# devre.net
KiCad netlist of a schematic drawn in EAGLE
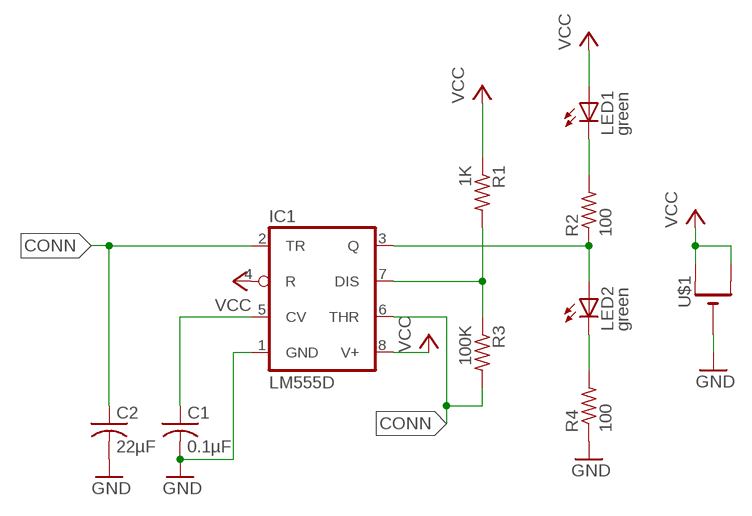
[diagram p0: schematic, sheet 1]

(export (version "E")
  (design (tool "Eeschema 10.0.6"))
  (components
    (comp (ref "C1")
      (value "0.1µF")
      (footprint "eagle-import:C0805")
      (libsource (lib "eagle-import") (part "C-USC0805"))
    )
    (comp (ref "C2")
      (value "22µF")
      (footprint "eagle-import:C0805")
      (libsource (lib "eagle-import") (part "C-USC0805"))
    )
    (comp (ref "IC1")
      (value "LM555D")
      (footprint "eagle-import:SO08")
      (libsource (lib "eagle-import") (part "555DLM"))
    )
    (comp (ref "LED1")
      (value "green")
      (footprint "eagle-import:CHIP-LED0805")
      (libsource (lib "eagle-import") (part "LEDCHIP-LED0805"))
    )
    (comp (ref "LED2")
      (value "green")
      (footprint "eagle-import:CHIP-LED0805")
      (libsource (lib "eagle-import") (part "LEDCHIP-LED0805"))
    )
    (comp (ref "R1")
      (value "1K")
      (footprint "eagle-import:R0805")
      (libsource (lib "eagle-import") (part "R-US_R0805"))
    )
    (comp (ref "R2")
      (value "100")
      (footprint "eagle-import:R0805")
      (libsource (lib "eagle-import") (part "R-US_R0805"))
    )
    (comp (ref "R3")
      (value "100K")
      (footprint "eagle-import:R0805")
      (libsource (lib "eagle-import") (part "R-US_R0805"))
    )
    (comp (ref "R4")
      (value "100")
      (footprint "eagle-import:R0805")
      (libsource (lib "eagle-import") (part "R-US_R0805"))
    )
    (comp (ref "U$1")
      (value "CR1220SMT")
      (footprint "eagle-import:CR1220-SMD")
      (libsource (lib "eagle-import") (part "CR1220SMT"))
    )
  )
  (nets
    (net (code "1") (name "CONN") (class "Default")
      (node (ref "C2") (pin "1") (pinfunction "1_1") (pintype "passive"))
      (node (ref "IC1") (pin "2") (pinfunction "TR_2") (pintype "input"))
      (node (ref "IC1") (pin "6") (pinfunction "THR_6") (pintype "input"))
      (node (ref "R3") (pin "2") (pinfunction "2_2") (pintype "passive"))
    )
    (net (code "2") (name "GND") (class "Default")
      (node (ref "C1") (pin "2") (pinfunction "2_2") (pintype "passive"))
      (node (ref "C2") (pin "2") (pinfunction "2_2") (pintype "passive"))
      (node (ref "IC1") (pin "1") (pinfunction "GND_1") (pintype "power_in"))
      (node (ref "R4") (pin "1") (pinfunction "1_1") (pintype "passive"))
      (node (ref "U$1") (pin "-") (pinfunction "-_-") (pintype "passive"))
    )
    (net (code "3") (name "Net-(IC1-CV)") (class "Default")
      (node (ref "C1") (pin "1") (pinfunction "1_1") (pintype "passive"))
      (node (ref "IC1") (pin "5") (pinfunction "CV_5") (pintype "input"))
    )
    (net (code "4") (name "Net-(IC1-DIS)") (class "Default")
      (node (ref "IC1") (pin "7") (pinfunction "DIS_7") (pintype "input"))
      (node (ref "R1") (pin "2") (pinfunction "2_2") (pintype "passive"))
      (node (ref "R3") (pin "1") (pinfunction "1_1") (pintype "passive"))
    )
    (net (code "5") (name "Net-(IC1-Q)") (class "Default")
      (node (ref "IC1") (pin "3") (pinfunction "Q_3") (pintype "output"))
      (node (ref "LED2") (pin "A") (pinfunction "A_A") (pintype "passive"))
      (node (ref "R2") (pin "1") (pinfunction "1_1") (pintype "passive"))
    )
    (net (code "6") (name "Net-(LED1-PadC)") (class "Default")
      (node (ref "LED1") (pin "C") (pinfunction "C_C") (pintype "passive"))
      (node (ref "R2") (pin "2") (pinfunction "2_2") (pintype "passive"))
    )
    (net (code "7") (name "Net-(LED2-PadC)") (class "Default")
      (node (ref "LED2") (pin "C") (pinfunction "C_C") (pintype "passive"))
      (node (ref "R4") (pin "2") (pinfunction "2_2") (pintype "passive"))
    )
    (net (code "8") (name "VCC") (class "Default")
      (node (ref "IC1") (pin "4") (pinfunction "R_4") (pintype "input"))
      (node (ref "IC1") (pin "8") (pinfunction "V+_8") (pintype "power_in"))
      (node (ref "LED1") (pin "A") (pinfunction "A_A") (pintype "passive"))
      (node (ref "R1") (pin "1") (pinfunction "1_1") (pintype "passive"))
      (node (ref "U$1") (pin "+$1") (pinfunction "+_+$1") (pintype "passive"))
      (node (ref "U$1") (pin "+$2") (pinfunction "+1_+$2") (pintype "passive"))
    )
  )
)
